# LO.net
KiCad netlist of a schematic drawn in Altium Designer
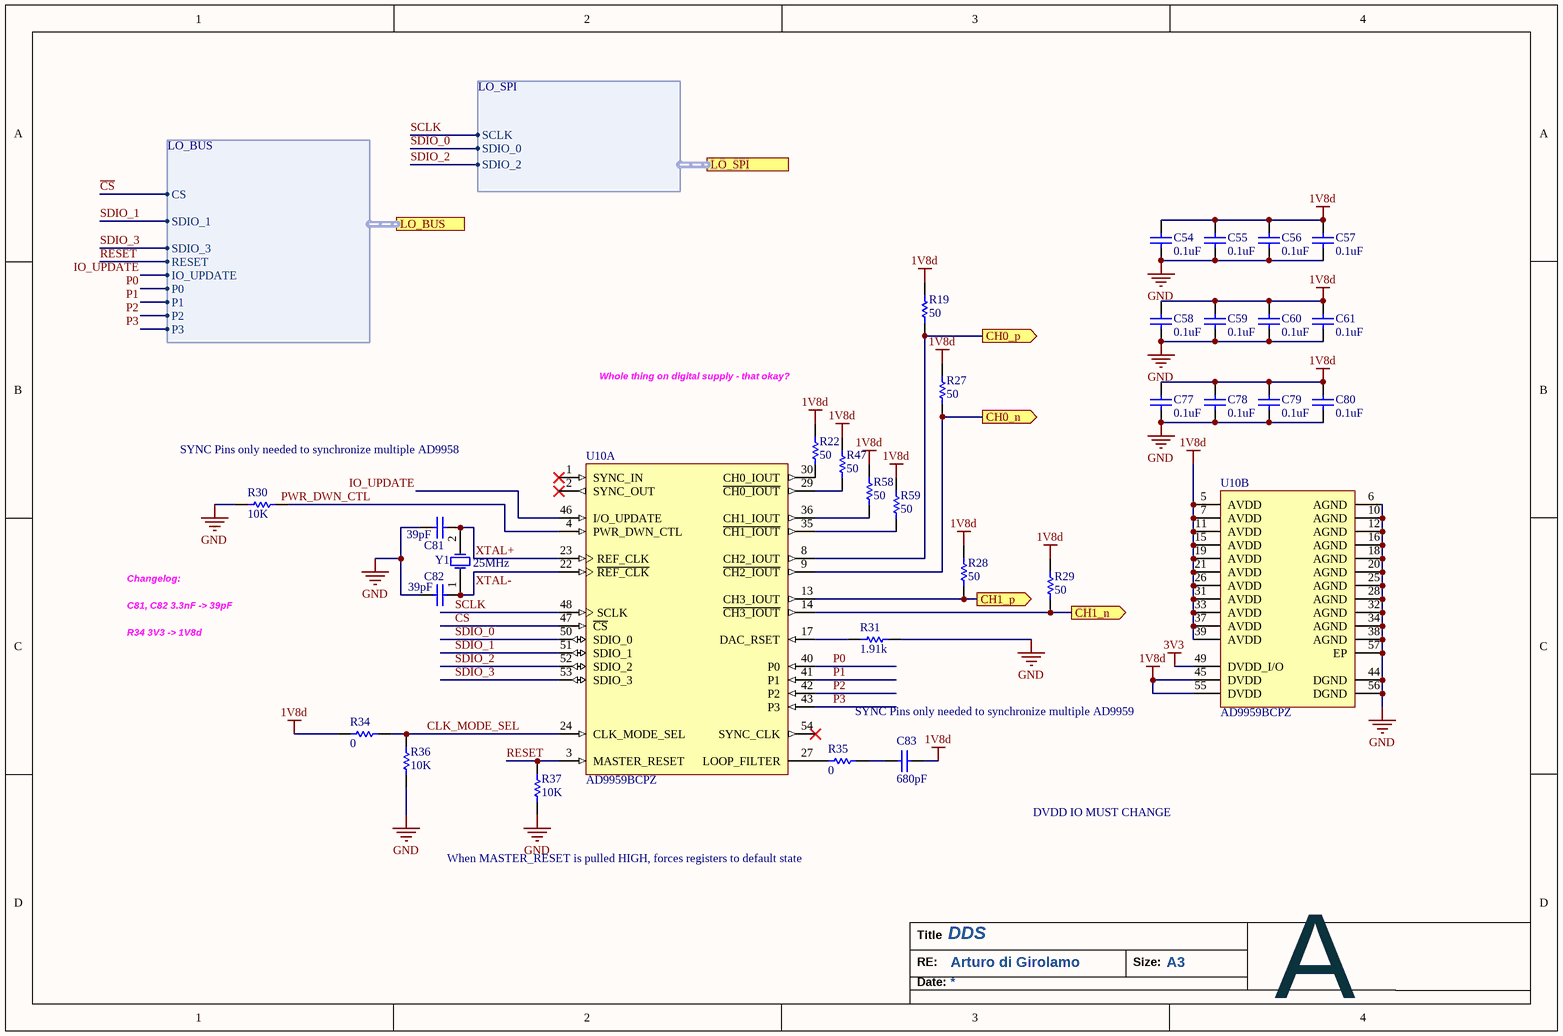
[diagram p0: LO.SchDoc]

(export (version "E")
  (design (tool "Eeschema 10.0.6"))
  (components
    (comp (ref "C54")
      (value "0.1uF")
      (footprint "0402_Cap")
      (description "Capacitor, 0.1uF, 0805")
      (libsource (lib "Arturo_Approved") (part "CL21B104KACNNNC"))
    )
    (comp (ref "C55")
      (value "0.1uF")
      (footprint "0402_Cap")
      (description "Capacitor, 0.1uF, 0805")
      (libsource (lib "Arturo_Approved") (part "CL21B104KACNNNC"))
    )
    (comp (ref "C56")
      (value "0.1uF")
      (footprint "0402_Cap")
      (description "Capacitor, 0.1uF, 0805")
      (libsource (lib "Arturo_Approved") (part "CL21B104KACNNNC"))
    )
    (comp (ref "C57")
      (value "0.1uF")
      (footprint "0402_Cap")
      (description "Capacitor, 0.1uF, 0805")
      (libsource (lib "Arturo_Approved") (part "CL21B104KACNNNC"))
    )
    (comp (ref "C58")
      (value "0.1uF")
      (footprint "0402_Cap")
      (description "Capacitor, 0.1uF, 0805")
      (libsource (lib "Arturo_Approved") (part "CL21B104KACNNNC"))
    )
    (comp (ref "C59")
      (value "0.1uF")
      (footprint "0402_Cap")
      (description "Capacitor, 0.1uF, 0805")
      (libsource (lib "Arturo_Approved") (part "CL21B104KACNNNC"))
    )
    (comp (ref "C60")
      (value "0.1uF")
      (footprint "0402_Cap")
      (description "Capacitor, 0.1uF, 0805")
      (libsource (lib "Arturo_Approved") (part "CL21B104KACNNNC"))
    )
    (comp (ref "C61")
      (value "0.1uF")
      (footprint "0402_Cap")
      (description "Capacitor, 0.1uF, 0805")
      (libsource (lib "Arturo_Approved") (part "CL21B104KACNNNC"))
    )
    (comp (ref "C77")
      (value "0.1uF")
      (footprint "0402_Cap")
      (description "Capacitor, 0.1uF, 0805")
      (libsource (lib "Arturo_Approved") (part "CL21B104KACNNNC"))
    )
    (comp (ref "C78")
      (value "0.1uF")
      (footprint "0402_Cap")
      (description "Capacitor, 0.1uF, 0805")
      (libsource (lib "Arturo_Approved") (part "CL21B104KACNNNC"))
    )
    (comp (ref "C79")
      (value "0.1uF")
      (footprint "0402_Cap")
      (description "Capacitor, 0.1uF, 0805")
      (libsource (lib "Arturo_Approved") (part "CL21B104KACNNNC"))
    )
    (comp (ref "C80")
      (value "0.1uF")
      (footprint "0402_Cap")
      (description "Capacitor, 0.1uF, 0805")
      (libsource (lib "Arturo_Approved") (part "CL21B104KACNNNC"))
    )
    (comp (ref "C81")
      (value "39pF")
      (footprint "0402_Cap")
      (description "Capacitor, 3.3nF, 0805")
      (libsource (lib "Arturo_Approved") (part "C0805C332KARACAUTO"))
    )
    (comp (ref "C82")
      (value "39pF")
      (footprint "0402_Cap")
      (description "Capacitor, 3.3nF, 0805")
      (libsource (lib "Arturo_Approved") (part "C0805C332KARACAUTO"))
    )
    (comp (ref "C83")
      (value "680pF")
      (footprint "0402_Cap")
      (description "Capacitor, 22uF, 0805, 25V")
      (libsource (lib "Arturo_Approved") (part "GRM21BR61E226ME44L"))
    )
    (comp (ref "R19")
      (value "50")
      (footprint "0402_Res")
      (description "0 ohm jumper")
      (libsource (lib "Arturo_Approved") (part "RMCF0805ZT0R00"))
    )
    (comp (ref "R22")
      (value "50")
      (footprint "0402_Res")
      (description "0 ohm jumper")
      (libsource (lib "Arturo_Approved") (part "RMCF0805ZT0R00"))
    )
    (comp (ref "R27")
      (value "50")
      (footprint "0402_Res")
      (description "0 ohm jumper")
      (libsource (lib "Arturo_Approved") (part "RMCF0805ZT0R00"))
    )
    (comp (ref "R28")
      (value "50")
      (footprint "0402_Res")
      (description "0 ohm jumper")
      (libsource (lib "Arturo_Approved") (part "RMCF0805ZT0R00"))
    )
    (comp (ref "R29")
      (value "50")
      (footprint "0402_Res")
      (description "0 ohm jumper")
      (libsource (lib "Arturo_Approved") (part "RMCF0805ZT0R00"))
    )
    (comp (ref "R30")
      (value "10K")
      (footprint "0402_Res")
      (description "10K 1% 1/4W")
      (libsource (lib "Arturo_Approved") (part "RNCP0805FTD10K0"))
    )
    (comp (ref "R31")
      (value "1.91k")
      (footprint "0402_Res")
      (description "0 ohm jumper")
      (libsource (lib "Arturo_Approved") (part "RMCF0805ZT0R00"))
    )
    (comp (ref "R34")
      (value "0")
      (footprint "0402_Res")
      (description "0 ohm jumper")
      (libsource (lib "Arturo_Approved") (part "RMCF0805ZT0R00"))
    )
    (comp (ref "R35")
      (value "0")
      (footprint "0402_Res")
      (description "0 ohm jumper")
      (libsource (lib "Arturo_Approved") (part "RMCF0805ZT0R00"))
    )
    (comp (ref "R36")
      (value "10K")
      (footprint "0402_Res")
      (description "10K 1% 1/4W")
      (libsource (lib "Arturo_Approved") (part "RNCP0805FTD10K0"))
    )
    (comp (ref "R37")
      (value "10K")
      (footprint "0402_Res")
      (description "10K 1% 1/4W")
      (libsource (lib "Arturo_Approved") (part "RNCP0805FTD10K0"))
    )
    (comp (ref "R47")
      (value "50")
      (footprint "0402_Res")
      (description "0 ohm jumper")
      (libsource (lib "Arturo_Approved") (part "RMCF0805ZT0R00"))
    )
    (comp (ref "R58")
      (value "50")
      (footprint "0402_Res")
      (description "0 ohm jumper")
      (libsource (lib "Arturo_Approved") (part "RMCF0805ZT0R00"))
    )
    (comp (ref "R59")
      (value "50")
      (footprint "0402_Res")
      (description "0 ohm jumper")
      (libsource (lib "Arturo_Approved") (part "RMCF0805ZT0R00"))
    )
    (comp (ref "U10")
      (value "AD9959BCPZ")
      (footprint "ADI-CP-56-1_M")
      (description "4-Channel, 500 MSPS DDS with 10-Bit DACs, Serial, CP-56-1, 260 Tray, Pb-Free")
      (libsource (lib "Altium Content Vault") (part "ADI-AD9959-CP-56-1"))
    )
    (comp (ref "Y1")
      (value "25MHz")
      (footprint "XTAL_ECS-160-20-4X")
      (description "Crystal Oscillator")
      (fields (field (name "PUBLISHER") "Altium Limited"))
      (libsource (lib "Miscellaneous Devices") (part "XTAL"))
    )
  )
  (nets
    (net (code "3") (name "/CH0_n") (class "Default")
      (node (ref "R27") (pin "1") (pinfunction "1_1") (pintype "passive"))
      (node (ref "U10") (pin "9") (pinfunction "~{CH2_IOUT}_9") (pintype "output"))
    )
    (net (code "4") (name "/CH0_p") (class "Default")
      (node (ref "R19") (pin "1") (pinfunction "1_1") (pintype "passive"))
      (node (ref "U10") (pin "8") (pinfunction "CH2_IOUT_8") (pintype "output"))
    )
    (net (code "5") (name "/CH1_n") (class "Default")
      (node (ref "R29") (pin "1") (pinfunction "1_1") (pintype "passive"))
      (node (ref "U10") (pin "14") (pinfunction "~{CH3_IOUT}_14") (pintype "output"))
    )
    (net (code "6") (name "/CH1_p") (class "Default")
      (node (ref "R28") (pin "1") (pinfunction "1_1") (pintype "passive"))
      (node (ref "U10") (pin "13") (pinfunction "CH3_IOUT_13") (pintype "output"))
    )
    (net (code "7") (name "/CLK_MODE_SEL") (class "Default")
      (node (ref "R34") (pin "2") (pinfunction "2_2") (pintype "passive"))
      (node (ref "R36") (pin "2") (pinfunction "2_2") (pintype "passive"))
      (node (ref "U10") (pin "24") (pinfunction "CLK_MODE_SEL_24") (pintype "input"))
    )
    (net (code "8") (name "/IO_UPDATE") (class "Default")
      (node (ref "U10") (pin "46") (pinfunction "I/O_UPDATE_46") (pintype "input"))
    )
    (net (code "9") (name "/P0") (class "Default")
      (node (ref "U10") (pin "40") (pinfunction "P0_40") (pintype "input"))
    )
    (net (code "10") (name "/P1") (class "Default")
      (node (ref "U10") (pin "41") (pinfunction "P1_41") (pintype "input"))
    )
    (net (code "11") (name "/P2") (class "Default")
      (node (ref "U10") (pin "42") (pinfunction "P2_42") (pintype "input"))
    )
    (net (code "12") (name "/P3") (class "Default")
      (node (ref "U10") (pin "43") (pinfunction "P3_43") (pintype "input"))
    )
    (net (code "14") (name "/RESET") (class "Default")
      (node (ref "R37") (pin "2") (pinfunction "2_2") (pintype "passive"))
      (node (ref "U10") (pin "3") (pinfunction "MASTER_RESET_3") (pintype "input"))
    )
    (net (code "15") (name "/SCLK") (class "Default")
      (node (ref "U10") (pin "48") (pinfunction "SCLK_48") (pintype "input"))
    )
    (net (code "16") (name "/SDIO_0") (class "Default")
      (node (ref "U10") (pin "50") (pinfunction "SDIO_0_50") (pintype "bidirectional"))
    )
    (net (code "17") (name "/SDIO_1") (class "Default")
      (node (ref "U10") (pin "51") (pinfunction "SDIO_1_51") (pintype "bidirectional"))
    )
    (net (code "18") (name "/SDIO_2") (class "Default")
      (node (ref "U10") (pin "52") (pinfunction "SDIO_2_52") (pintype "bidirectional"))
    )
    (net (code "19") (name "/SDIO_3") (class "Default")
      (node (ref "U10") (pin "53") (pinfunction "SDIO_3_53") (pintype "bidirectional"))
    )
    (net (code "20") (name "/XTAL+") (class "Default")
      (node (ref "C81") (pin "1") (pinfunction "1_1") (pintype "passive"))
      (node (ref "U10") (pin "23") (pinfunction "REF_CLK_23") (pintype "input"))
      (node (ref "Y1") (pin "2") (pinfunction "OSC2_2") (pintype "passive"))
    )
    (net (code "21") (name "/XTAL-") (class "Default")
      (node (ref "C82") (pin "1") (pinfunction "1_1") (pintype "passive"))
      (node (ref "U10") (pin "22") (pinfunction "~{REF_CLK}_22") (pintype "input"))
      (node (ref "Y1") (pin "1") (pinfunction "OSC1_1") (pintype "passive"))
    )
    (net (code "24") (name "/~{CS}") (class "Default")
      (node (ref "U10") (pin "47") (pinfunction "~{CS}_47") (pintype "input"))
    )
    (net (code "25") (name "1V8d") (class "Default")
      (node (ref "C54") (pin "2") (pinfunction "2_2") (pintype "passive"))
      (node (ref "C55") (pin "2") (pinfunction "2_2") (pintype "passive"))
      (node (ref "C56") (pin "2") (pinfunction "2_2") (pintype "passive"))
      (node (ref "C57") (pin "2") (pinfunction "2_2") (pintype "passive"))
      (node (ref "C58") (pin "2") (pinfunction "2_2") (pintype "passive"))
      (node (ref "C59") (pin "2") (pinfunction "2_2") (pintype "passive"))
      (node (ref "C60") (pin "2") (pinfunction "2_2") (pintype "passive"))
      (node (ref "C61") (pin "2") (pinfunction "2_2") (pintype "passive"))
      (node (ref "C77") (pin "2") (pinfunction "2_2") (pintype "passive"))
      (node (ref "C78") (pin "2") (pinfunction "2_2") (pintype "passive"))
      (node (ref "C79") (pin "2") (pinfunction "2_2") (pintype "passive"))
      (node (ref "C80") (pin "2") (pinfunction "2_2") (pintype "passive"))
      (node (ref "C83") (pin "2") (pinfunction "2_2") (pintype "passive"))
      (node (ref "R19") (pin "2") (pinfunction "2_2") (pintype "passive"))
      (node (ref "R22") (pin "2") (pinfunction "2_2") (pintype "passive"))
      (node (ref "R27") (pin "2") (pinfunction "2_2") (pintype "passive"))
      (node (ref "R28") (pin "2") (pinfunction "2_2") (pintype "passive"))
      (node (ref "R29") (pin "2") (pinfunction "2_2") (pintype "passive"))
      (node (ref "R34") (pin "1") (pinfunction "1_1") (pintype "passive"))
      (node (ref "R47") (pin "2") (pinfunction "2_2") (pintype "passive"))
      (node (ref "R58") (pin "2") (pinfunction "2_2") (pintype "passive"))
      (node (ref "R59") (pin "2") (pinfunction "2_2") (pintype "passive"))
      (node (ref "U10") (pin "11") (pinfunction "AVDD_11") (pintype "power_in"))
      (node (ref "U10") (pin "15") (pinfunction "AVDD_15") (pintype "power_in"))
      (node (ref "U10") (pin "19") (pinfunction "AVDD_19") (pintype "power_in"))
      (node (ref "U10") (pin "21") (pinfunction "AVDD_21") (pintype "power_in"))
      (node (ref "U10") (pin "26") (pinfunction "AVDD_26") (pintype "power_in"))
      (node (ref "U10") (pin "31") (pinfunction "AVDD_31") (pintype "power_in"))
      (node (ref "U10") (pin "33") (pinfunction "AVDD_33") (pintype "power_in"))
      (node (ref "U10") (pin "37") (pinfunction "AVDD_37") (pintype "power_in"))
      (node (ref "U10") (pin "39") (pinfunction "AVDD_39") (pintype "power_in"))
      (node (ref "U10") (pin "45") (pinfunction "DVDD_45") (pintype "power_in"))
      (node (ref "U10") (pin "5") (pinfunction "AVDD_5") (pintype "power_in"))
      (node (ref "U10") (pin "55") (pinfunction "DVDD_55") (pintype "power_in"))
      (node (ref "U10") (pin "7") (pinfunction "AVDD_7") (pintype "power_in"))
    )
    (net (code "26") (name "3V3") (class "Default")
      (node (ref "U10") (pin "49") (pinfunction "DVDD_I/O_49") (pintype "power_in"))
    )
    (net (code "27") (name "GND") (class "Default")
      (node (ref "C54") (pin "1") (pinfunction "1_1") (pintype "passive"))
      (node (ref "C55") (pin "1") (pinfunction "1_1") (pintype "passive"))
      (node (ref "C56") (pin "1") (pinfunction "1_1") (pintype "passive"))
      (node (ref "C57") (pin "1") (pinfunction "1_1") (pintype "passive"))
      (node (ref "C58") (pin "1") (pinfunction "1_1") (pintype "passive"))
      (node (ref "C59") (pin "1") (pinfunction "1_1") (pintype "passive"))
      (node (ref "C60") (pin "1") (pinfunction "1_1") (pintype "passive"))
      (node (ref "C61") (pin "1") (pinfunction "1_1") (pintype "passive"))
      (node (ref "C77") (pin "1") (pinfunction "1_1") (pintype "passive"))
      (node (ref "C78") (pin "1") (pinfunction "1_1") (pintype "passive"))
      (node (ref "C79") (pin "1") (pinfunction "1_1") (pintype "passive"))
      (node (ref "C80") (pin "1") (pinfunction "1_1") (pintype "passive"))
      (node (ref "C81") (pin "2") (pinfunction "2_2") (pintype "passive"))
      (node (ref "C82") (pin "2") (pinfunction "2_2") (pintype "passive"))
      (node (ref "R30") (pin "1") (pinfunction "1_1") (pintype "passive"))
      (node (ref "R31") (pin "2") (pinfunction "2_2") (pintype "passive"))
      (node (ref "R36") (pin "1") (pinfunction "1_1") (pintype "passive"))
      (node (ref "R37") (pin "1") (pinfunction "1_1") (pintype "passive"))
      (node (ref "U10") (pin "10") (pinfunction "AGND_10") (pintype "power_in"))
      (node (ref "U10") (pin "12") (pinfunction "AGND_12") (pintype "power_in"))
      (node (ref "U10") (pin "16") (pinfunction "AGND_16") (pintype "power_in"))
      (node (ref "U10") (pin "18") (pinfunction "AGND_18") (pintype "power_in"))
      (node (ref "U10") (pin "20") (pinfunction "AGND_20") (pintype "power_in"))
      (node (ref "U10") (pin "25") (pinfunction "AGND_25") (pintype "power_in"))
      (node (ref "U10") (pin "28") (pinfunction "AGND_28") (pintype "power_in"))
      (node (ref "U10") (pin "32") (pinfunction "AGND_32") (pintype "power_in"))
      (node (ref "U10") (pin "34") (pinfunction "AGND_34") (pintype "power_in"))
      (node (ref "U10") (pin "38") (pinfunction "AGND_38") (pintype "power_in"))
      (node (ref "U10") (pin "44") (pinfunction "DGND_44") (pintype "power_in"))
      (node (ref "U10") (pin "56") (pinfunction "DGND_56") (pintype "power_in"))
      (node (ref "U10") (pin "57") (pinfunction "EP_57") (pintype "power_in"))
      (node (ref "U10") (pin "6") (pinfunction "AGND_6") (pintype "power_in"))
    )
    (net (code "28") (name "Net-(C83-Pad1)") (class "Default")
      (node (ref "C83") (pin "1") (pinfunction "1_1") (pintype "passive"))
      (node (ref "R35") (pin "2") (pinfunction "2_2") (pintype "passive"))
    )
    (net (code "29") (name "Net-(U10A-CH0_IOUT)") (class "Default")
      (node (ref "R22") (pin "1") (pinfunction "1_1") (pintype "passive"))
      (node (ref "U10") (pin "30") (pinfunction "CH0_IOUT_30") (pintype "output"))
    )
    (net (code "30") (name "Net-(U10A-CH1_IOUT)") (class "Default")
      (node (ref "R58") (pin "1") (pinfunction "1_1") (pintype "passive"))
      (node (ref "U10") (pin "36") (pinfunction "CH1_IOUT_36") (pintype "output"))
    )
    (net (code "31") (name "Net-(U10A-DAC_RSET)") (class "Default")
      (node (ref "R31") (pin "1") (pinfunction "1_1") (pintype "passive"))
      (node (ref "U10") (pin "17") (pinfunction "DAC_RSET_17") (pintype "input"))
    )
    (net (code "32") (name "Net-(U10A-LOOP_FILTER)") (class "Default")
      (node (ref "R35") (pin "1") (pinfunction "1_1") (pintype "passive"))
      (node (ref "U10") (pin "27") (pinfunction "LOOP_FILTER_27") (pintype "passive"))
    )
    (net (code "33") (name "Net-(U10A-PWR_DWN_CTL)") (class "Default")
      (node (ref "R30") (pin "2") (pinfunction "2_2") (pintype "passive"))
      (node (ref "U10") (pin "4") (pinfunction "PWR_DWN_CTL_4") (pintype "input"))
    )
    (net (code "34") (name "Net-(U10A-~{CH0_IOUT})") (class "Default")
      (node (ref "R47") (pin "1") (pinfunction "1_1") (pintype "passive"))
      (node (ref "U10") (pin "29") (pinfunction "~{CH0_IOUT}_29") (pintype "output"))
    )
    (net (code "35") (name "Net-(U10A-~{CH1_IOUT})") (class "Default")
      (node (ref "R59") (pin "1") (pinfunction "1_1") (pintype "passive"))
      (node (ref "U10") (pin "35") (pinfunction "~{CH1_IOUT}_35") (pintype "output"))
    )
    (net (code "36") (name "unconnected-(U10A-SYNC_CLK-Pad54)") (class "Default")
      (node (ref "U10") (pin "54") (pinfunction "SYNC_CLK_54") (pintype "output+no_connect"))
    )
    (net (code "37") (name "unconnected-(U10A-SYNC_IN-Pad1)") (class "Default")
      (node (ref "U10") (pin "1") (pinfunction "SYNC_IN_1") (pintype "input+no_connect"))
    )
    (net (code "38") (name "unconnected-(U10A-SYNC_OUT-Pad2)") (class "Default")
      (node (ref "U10") (pin "2") (pinfunction "SYNC_OUT_2") (pintype "output+no_connect"))
    )
  )
)
